# Small_Relay.net
KiCad netlist of a schematic drawn in Altium Designer
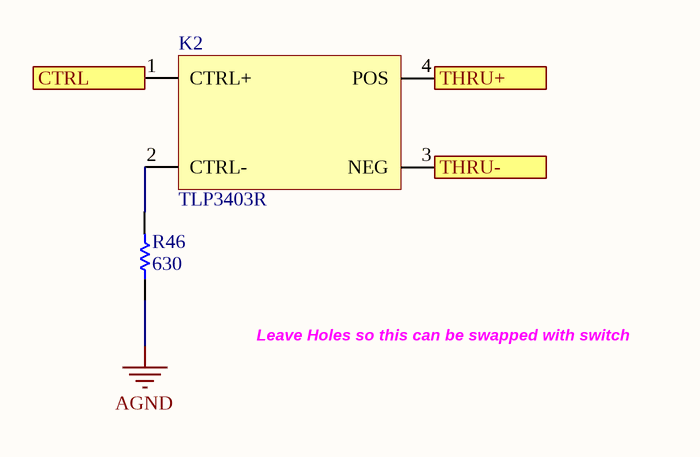
[diagram p0: Small_Relay.SchDoc]

(export (version "E")
  (design (tool "Eeschema 10.0.6"))
  (components
    (comp (ref "K2")
      (value "TLP3403R")
      (footprint "VSONR4")
      (libsource (lib "Arturo_Approved") (part "TLP3403R"))
    )
    (comp (ref "R46")
      (value "630")
      (footprint "0402_Res")
      (description "7.5K 1% 1/4W")
      (libsource (lib "Arturo_Approved") (part "ERJ-PB6D7501V"))
    )
  )
  (nets
    (net (code "1") (name "/CTRL") (class "Default")
      (node (ref "K2") (pin "1") (pinfunction "CTRL+_1") (pintype "passive"))
    )
    (net (code "2") (name "/THRU+") (class "Default")
      (node (ref "K2") (pin "4") (pinfunction "POS_4") (pintype "passive"))
    )
    (net (code "3") (name "/THRU-") (class "Default")
      (node (ref "K2") (pin "3") (pinfunction "NEG_3") (pintype "passive"))
    )
    (net (code "4") (name "AGND") (class "Default")
      (node (ref "R46") (pin "1") (pinfunction "1_1") (pintype "passive"))
    )
    (net (code "5") (name "Net-(K2-CTRL-)") (class "Default")
      (node (ref "K2") (pin "2") (pinfunction "CTRL-_2") (pintype "passive"))
      (node (ref "R46") (pin "2") (pinfunction "2_2") (pintype "passive"))
    )
  )
)
